# DIOT_signal_routing.net
KiCad netlist of a schematic drawn in Altium Designer
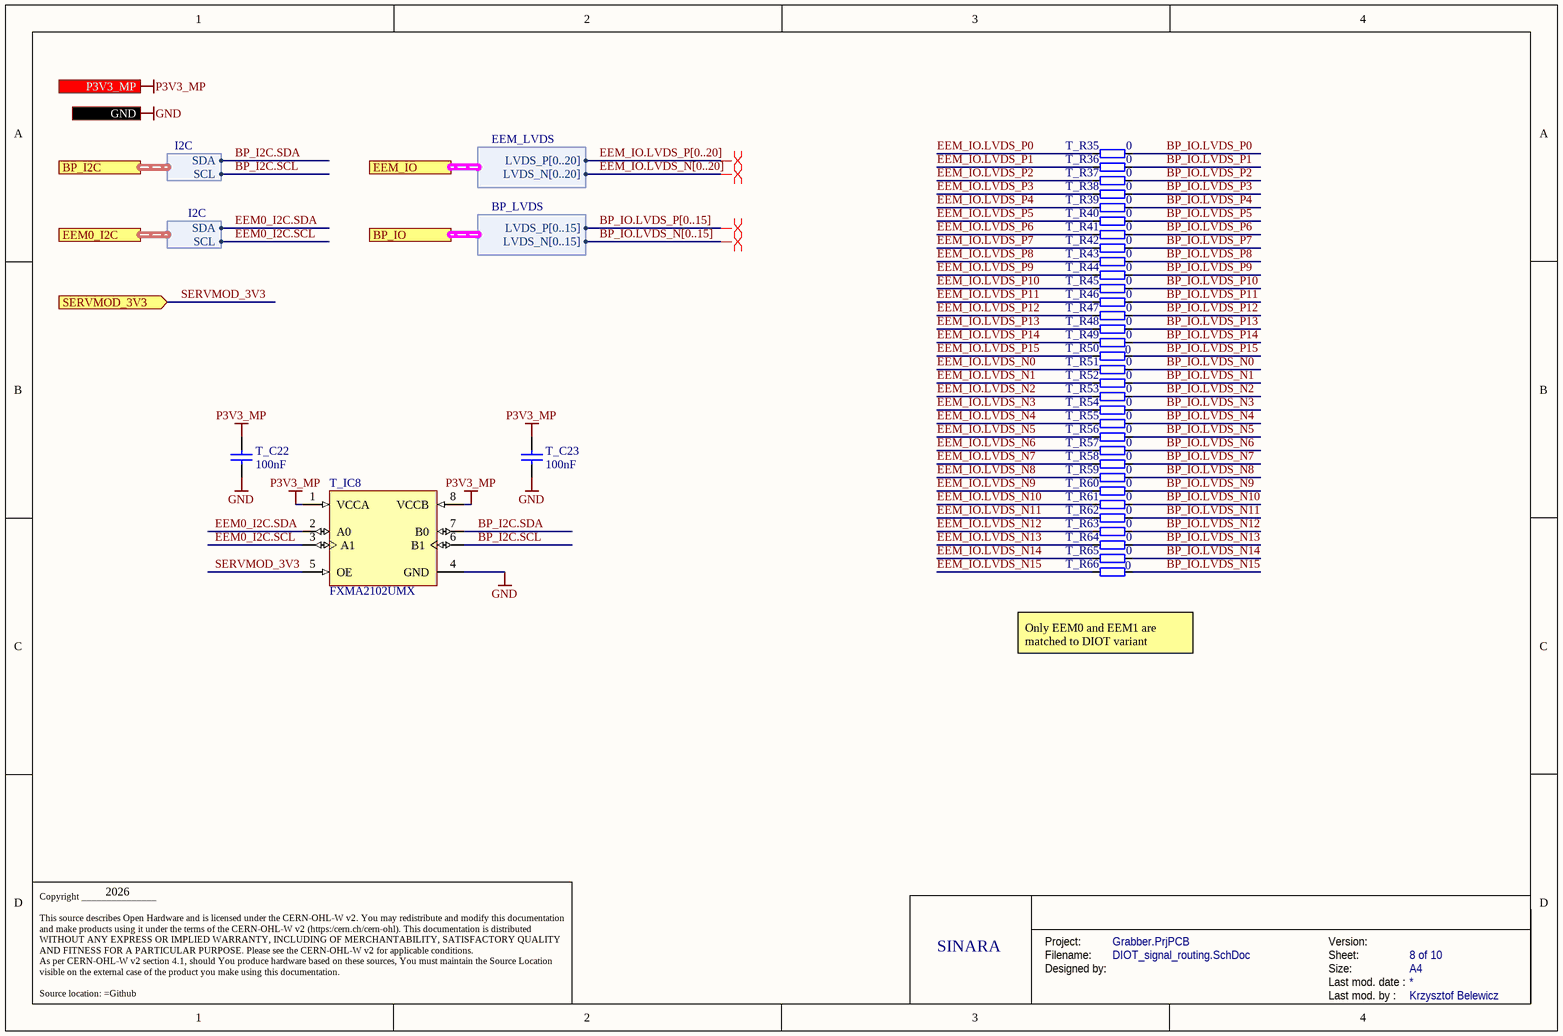
[diagram p0: DIOT_signal_routing.SchDoc]

(export (version "E")
  (design (tool "Eeschema 10.0.6"))
  (components
    (comp (ref "T_C22")
      (value "100nF")
      (footprint "CAPC1005X55N")
      (description "Non-polarised capacitor")
      (fields
        (field (name "PART NUMBER") "CC0402_100NF_50V_10%_X7R")
        (field (name "VOLTAGE") "50V")
        (field (name "AUTHOR") "CERN DEM MR")
      )
      (libsource (lib "Capacitors") (part "Capacitor - non polarized"))
    )
    (comp (ref "T_C23")
      (value "100nF")
      (footprint "CAPC1005X55N")
      (description "Non-polarised capacitor")
      (fields
        (field (name "PART NUMBER") "CC0402_100NF_50V_10%_X7R")
        (field (name "VOLTAGE") "50V")
        (field (name "AUTHOR") "CERN DEM MR")
      )
      (libsource (lib "Capacitors") (part "Capacitor - non polarized"))
    )
    (comp (ref "T_IC8")
      (value "FXMA2102UMX")
      (footprint "FXMA2102UMX")
      (description "Dual Supply 2-Bit Voltage Translator/Buffer/Repeater Isolator for I2C Applications")
      (fields (field (name "MANUFACTURER") "Onsemi"))
      (libsource (lib "TechnoSystem Workspace") (part "FXMA2102UMX"))
    )
    (comp (ref "T_R35")
      (value "0")
      (footprint "RESC1005X40N")
      (description "Resistor")
      (fields
        (field (name "PART NUMBER") "R0402_0R_JUMPER")
        (field (name "MANUFACTURER") "GENERIC")
        (field (name "AUTHOR") "CERN DEM JLC")
      )
      (libsource (lib "Resistors") (part "Resistor"))
    )
    (comp (ref "T_R36")
      (value "0")
      (footprint "RESC1005X40N")
      (description "Resistor")
      (fields
        (field (name "PART NUMBER") "R0402_0R_JUMPER")
        (field (name "MANUFACTURER") "GENERIC")
        (field (name "AUTHOR") "CERN DEM JLC")
      )
      (libsource (lib "Resistors") (part "Resistor"))
    )
    (comp (ref "T_R37")
      (value "0")
      (footprint "RESC1005X40N")
      (description "Resistor")
      (fields
        (field (name "PART NUMBER") "R0402_0R_JUMPER")
        (field (name "MANUFACTURER") "GENERIC")
        (field (name "AUTHOR") "CERN DEM JLC")
      )
      (libsource (lib "Resistors") (part "Resistor"))
    )
    (comp (ref "T_R38")
      (value "0")
      (footprint "RESC1005X40N")
      (description "Resistor")
      (fields
        (field (name "PART NUMBER") "R0402_0R_JUMPER")
        (field (name "MANUFACTURER") "GENERIC")
        (field (name "AUTHOR") "CERN DEM JLC")
      )
      (libsource (lib "Resistors") (part "Resistor"))
    )
    (comp (ref "T_R39")
      (value "0")
      (footprint "RESC1005X40N")
      (description "Resistor")
      (fields
        (field (name "PART NUMBER") "R0402_0R_JUMPER")
        (field (name "MANUFACTURER") "GENERIC")
        (field (name "AUTHOR") "CERN DEM JLC")
      )
      (libsource (lib "Resistors") (part "Resistor"))
    )
    (comp (ref "T_R40")
      (value "0")
      (footprint "RESC1005X40N")
      (description "Resistor")
      (fields
        (field (name "PART NUMBER") "R0402_0R_JUMPER")
        (field (name "MANUFACTURER") "GENERIC")
        (field (name "AUTHOR") "CERN DEM JLC")
      )
      (libsource (lib "Resistors") (part "Resistor"))
    )
    (comp (ref "T_R41")
      (value "0")
      (footprint "RESC1005X40N")
      (description "Resistor")
      (fields
        (field (name "PART NUMBER") "R0402_0R_JUMPER")
        (field (name "MANUFACTURER") "GENERIC")
        (field (name "AUTHOR") "CERN DEM JLC")
      )
      (libsource (lib "Resistors") (part "Resistor"))
    )
    (comp (ref "T_R42")
      (value "0")
      (footprint "RESC1005X40N")
      (description "Resistor")
      (fields
        (field (name "PART NUMBER") "R0402_0R_JUMPER")
        (field (name "MANUFACTURER") "GENERIC")
        (field (name "AUTHOR") "CERN DEM JLC")
      )
      (libsource (lib "Resistors") (part "Resistor"))
    )
    (comp (ref "T_R43")
      (value "0")
      (footprint "RESC1005X40N")
      (description "Resistor")
      (fields
        (field (name "PART NUMBER") "R0402_0R_JUMPER")
        (field (name "MANUFACTURER") "GENERIC")
        (field (name "AUTHOR") "CERN DEM JLC")
      )
      (libsource (lib "Resistors") (part "Resistor"))
    )
    (comp (ref "T_R44")
      (value "0")
      (footprint "RESC1005X40N")
      (description "Resistor")
      (fields
        (field (name "PART NUMBER") "R0402_0R_JUMPER")
        (field (name "MANUFACTURER") "GENERIC")
        (field (name "AUTHOR") "CERN DEM JLC")
      )
      (libsource (lib "Resistors") (part "Resistor"))
    )
    (comp (ref "T_R45")
      (value "0")
      (footprint "RESC1005X40N")
      (description "Resistor")
      (fields
        (field (name "PART NUMBER") "R0402_0R_JUMPER")
        (field (name "MANUFACTURER") "GENERIC")
        (field (name "AUTHOR") "CERN DEM JLC")
      )
      (libsource (lib "Resistors") (part "Resistor"))
    )
    (comp (ref "T_R46")
      (value "0")
      (footprint "RESC1005X40N")
      (description "Resistor")
      (fields
        (field (name "PART NUMBER") "R0402_0R_JUMPER")
        (field (name "MANUFACTURER") "GENERIC")
        (field (name "AUTHOR") "CERN DEM JLC")
      )
      (libsource (lib "Resistors") (part "Resistor"))
    )
    (comp (ref "T_R47")
      (value "0")
      (footprint "RESC1005X40N")
      (description "Resistor")
      (fields
        (field (name "PART NUMBER") "R0402_0R_JUMPER")
        (field (name "MANUFACTURER") "GENERIC")
        (field (name "AUTHOR") "CERN DEM JLC")
      )
      (libsource (lib "Resistors") (part "Resistor"))
    )
    (comp (ref "T_R48")
      (value "0")
      (footprint "RESC1005X40N")
      (description "Resistor")
      (fields
        (field (name "PART NUMBER") "R0402_0R_JUMPER")
        (field (name "MANUFACTURER") "GENERIC")
        (field (name "AUTHOR") "CERN DEM JLC")
      )
      (libsource (lib "Resistors") (part "Resistor"))
    )
    (comp (ref "T_R49")
      (value "0")
      (footprint "RESC1005X40N")
      (description "Resistor")
      (fields
        (field (name "PART NUMBER") "R0402_0R_JUMPER")
        (field (name "MANUFACTURER") "GENERIC")
        (field (name "AUTHOR") "CERN DEM JLC")
      )
      (libsource (lib "Resistors") (part "Resistor"))
    )
    (comp (ref "T_R50")
      (value "0")
      (footprint "RESC1005X40N")
      (description "Resistor")
      (fields
        (field (name "PART NUMBER") "R0402_0R_JUMPER")
        (field (name "MANUFACTURER") "GENERIC")
        (field (name "AUTHOR") "CERN DEM JLC")
      )
      (libsource (lib "Resistors") (part "Resistor"))
    )
    (comp (ref "T_R51")
      (value "0")
      (footprint "RESC1005X40N")
      (description "Resistor")
      (fields
        (field (name "PART NUMBER") "R0402_0R_JUMPER")
        (field (name "MANUFACTURER") "GENERIC")
        (field (name "AUTHOR") "CERN DEM JLC")
      )
      (libsource (lib "Resistors") (part "Resistor"))
    )
    (comp (ref "T_R52")
      (value "0")
      (footprint "RESC1005X40N")
      (description "Resistor")
      (fields
        (field (name "PART NUMBER") "R0402_0R_JUMPER")
        (field (name "MANUFACTURER") "GENERIC")
        (field (name "AUTHOR") "CERN DEM JLC")
      )
      (libsource (lib "Resistors") (part "Resistor"))
    )
    (comp (ref "T_R53")
      (value "0")
      (footprint "RESC1005X40N")
      (description "Resistor")
      (fields
        (field (name "PART NUMBER") "R0402_0R_JUMPER")
        (field (name "MANUFACTURER") "GENERIC")
        (field (name "AUTHOR") "CERN DEM JLC")
      )
      (libsource (lib "Resistors") (part "Resistor"))
    )
    (comp (ref "T_R54")
      (value "0")
      (footprint "RESC1005X40N")
      (description "Resistor")
      (fields
        (field (name "PART NUMBER") "R0402_0R_JUMPER")
        (field (name "MANUFACTURER") "GENERIC")
        (field (name "AUTHOR") "CERN DEM JLC")
      )
      (libsource (lib "Resistors") (part "Resistor"))
    )
    (comp (ref "T_R55")
      (value "0")
      (footprint "RESC1005X40N")
      (description "Resistor")
      (fields
        (field (name "PART NUMBER") "R0402_0R_JUMPER")
        (field (name "MANUFACTURER") "GENERIC")
        (field (name "AUTHOR") "CERN DEM JLC")
      )
      (libsource (lib "Resistors") (part "Resistor"))
    )
    (comp (ref "T_R56")
      (value "0")
      (footprint "RESC1005X40N")
      (description "Resistor")
      (fields
        (field (name "PART NUMBER") "R0402_0R_JUMPER")
        (field (name "MANUFACTURER") "GENERIC")
        (field (name "AUTHOR") "CERN DEM JLC")
      )
      (libsource (lib "Resistors") (part "Resistor"))
    )
    (comp (ref "T_R57")
      (value "0")
      (footprint "RESC1005X40N")
      (description "Resistor")
      (fields
        (field (name "PART NUMBER") "R0402_0R_JUMPER")
        (field (name "MANUFACTURER") "GENERIC")
        (field (name "AUTHOR") "CERN DEM JLC")
      )
      (libsource (lib "Resistors") (part "Resistor"))
    )
    (comp (ref "T_R58")
      (value "0")
      (footprint "RESC1005X40N")
      (description "Resistor")
      (fields
        (field (name "PART NUMBER") "R0402_0R_JUMPER")
        (field (name "MANUFACTURER") "GENERIC")
        (field (name "AUTHOR") "CERN DEM JLC")
      )
      (libsource (lib "Resistors") (part "Resistor"))
    )
    (comp (ref "T_R59")
      (value "0")
      (footprint "RESC1005X40N")
      (description "Resistor")
      (fields
        (field (name "PART NUMBER") "R0402_0R_JUMPER")
        (field (name "MANUFACTURER") "GENERIC")
        (field (name "AUTHOR") "CERN DEM JLC")
      )
      (libsource (lib "Resistors") (part "Resistor"))
    )
    (comp (ref "T_R60")
      (value "0")
      (footprint "RESC1005X40N")
      (description "Resistor")
      (fields
        (field (name "PART NUMBER") "R0402_0R_JUMPER")
        (field (name "MANUFACTURER") "GENERIC")
        (field (name "AUTHOR") "CERN DEM JLC")
      )
      (libsource (lib "Resistors") (part "Resistor"))
    )
    (comp (ref "T_R61")
      (value "0")
      (footprint "RESC1005X40N")
      (description "Resistor")
      (fields
        (field (name "PART NUMBER") "R0402_0R_JUMPER")
        (field (name "MANUFACTURER") "GENERIC")
        (field (name "AUTHOR") "CERN DEM JLC")
      )
      (libsource (lib "Resistors") (part "Resistor"))
    )
    (comp (ref "T_R62")
      (value "0")
      (footprint "RESC1005X40N")
      (description "Resistor")
      (fields
        (field (name "PART NUMBER") "R0402_0R_JUMPER")
        (field (name "MANUFACTURER") "GENERIC")
        (field (name "AUTHOR") "CERN DEM JLC")
      )
      (libsource (lib "Resistors") (part "Resistor"))
    )
    (comp (ref "T_R63")
      (value "0")
      (footprint "RESC1005X40N")
      (description "Resistor")
      (fields
        (field (name "PART NUMBER") "R0402_0R_JUMPER")
        (field (name "MANUFACTURER") "GENERIC")
        (field (name "AUTHOR") "CERN DEM JLC")
      )
      (libsource (lib "Resistors") (part "Resistor"))
    )
    (comp (ref "T_R64")
      (value "0")
      (footprint "RESC1005X40N")
      (description "Resistor")
      (fields
        (field (name "PART NUMBER") "R0402_0R_JUMPER")
        (field (name "MANUFACTURER") "GENERIC")
        (field (name "AUTHOR") "CERN DEM JLC")
      )
      (libsource (lib "Resistors") (part "Resistor"))
    )
    (comp (ref "T_R65")
      (value "0")
      (footprint "RESC1005X40N")
      (description "Resistor")
      (fields
        (field (name "PART NUMBER") "R0402_0R_JUMPER")
        (field (name "MANUFACTURER") "GENERIC")
        (field (name "AUTHOR") "CERN DEM JLC")
      )
      (libsource (lib "Resistors") (part "Resistor"))
    )
    (comp (ref "T_R66")
      (value "0")
      (footprint "RESC1005X40N")
      (description "Resistor")
      (fields
        (field (name "PART NUMBER") "R0402_0R_JUMPER")
        (field (name "MANUFACTURER") "GENERIC")
        (field (name "AUTHOR") "CERN DEM JLC")
      )
      (libsource (lib "Resistors") (part "Resistor"))
    )
  )
  (nets
    (net (code "14") (name "/BP_I2C.SCL") (class "Default")
      (node (ref "T_IC8") (pin "6") (pinfunction "B1_6") (pintype "bidirectional"))
    )
    (net (code "15") (name "/BP_I2C.SDA") (class "Default")
      (node (ref "T_IC8") (pin "7") (pinfunction "B0_7") (pintype "bidirectional"))
    )
    (net (code "16") (name "/BP_IO.LVDS_N0") (class "Default")
      (node (ref "T_R51") (pin "1") (pinfunction "1_1") (pintype "passive"))
    )
    (net (code "17") (name "/BP_IO.LVDS_N1") (class "Default")
      (node (ref "T_R52") (pin "1") (pinfunction "1_1") (pintype "passive"))
    )
    (net (code "18") (name "/BP_IO.LVDS_N2") (class "Default")
      (node (ref "T_R53") (pin "1") (pinfunction "1_1") (pintype "passive"))
    )
    (net (code "19") (name "/BP_IO.LVDS_N3") (class "Default")
      (node (ref "T_R54") (pin "1") (pinfunction "1_1") (pintype "passive"))
    )
    (net (code "20") (name "/BP_IO.LVDS_N4") (class "Default")
      (node (ref "T_R55") (pin "1") (pinfunction "1_1") (pintype "passive"))
    )
    (net (code "21") (name "/BP_IO.LVDS_N5") (class "Default")
      (node (ref "T_R56") (pin "1") (pinfunction "1_1") (pintype "passive"))
    )
    (net (code "22") (name "/BP_IO.LVDS_N6") (class "Default")
      (node (ref "T_R57") (pin "1") (pinfunction "1_1") (pintype "passive"))
    )
    (net (code "23") (name "/BP_IO.LVDS_N7") (class "Default")
      (node (ref "T_R58") (pin "1") (pinfunction "1_1") (pintype "passive"))
    )
    (net (code "24") (name "/BP_IO.LVDS_N8") (class "Default")
      (node (ref "T_R59") (pin "1") (pinfunction "1_1") (pintype "passive"))
    )
    (net (code "25") (name "/BP_IO.LVDS_N9") (class "Default")
      (node (ref "T_R60") (pin "1") (pinfunction "1_1") (pintype "passive"))
    )
    (net (code "26") (name "/BP_IO.LVDS_N10") (class "Default")
      (node (ref "T_R61") (pin "1") (pinfunction "1_1") (pintype "passive"))
    )
    (net (code "27") (name "/BP_IO.LVDS_N11") (class "Default")
      (node (ref "T_R62") (pin "1") (pinfunction "1_1") (pintype "passive"))
    )
    (net (code "28") (name "/BP_IO.LVDS_N12") (class "Default")
      (node (ref "T_R63") (pin "1") (pinfunction "1_1") (pintype "passive"))
    )
    (net (code "29") (name "/BP_IO.LVDS_N13") (class "Default")
      (node (ref "T_R64") (pin "1") (pinfunction "1_1") (pintype "passive"))
    )
    (net (code "30") (name "/BP_IO.LVDS_N14") (class "Default")
      (node (ref "T_R65") (pin "1") (pinfunction "1_1") (pintype "passive"))
    )
    (net (code "31") (name "/BP_IO.LVDS_N15") (class "Default")
      (node (ref "T_R66") (pin "2") (pinfunction "2_2") (pintype "passive"))
    )
    (net (code "32") (name "/BP_IO.LVDS_P0") (class "Default")
      (node (ref "T_R35") (pin "1") (pinfunction "1_1") (pintype "passive"))
    )
    (net (code "33") (name "/BP_IO.LVDS_P1") (class "Default")
      (node (ref "T_R36") (pin "1") (pinfunction "1_1") (pintype "passive"))
    )
    (net (code "34") (name "/BP_IO.LVDS_P2") (class "Default")
      (node (ref "T_R37") (pin "1") (pinfunction "1_1") (pintype "passive"))
    )
    (net (code "35") (name "/BP_IO.LVDS_P3") (class "Default")
      (node (ref "T_R38") (pin "1") (pinfunction "1_1") (pintype "passive"))
    )
    (net (code "36") (name "/BP_IO.LVDS_P4") (class "Default")
      (node (ref "T_R39") (pin "1") (pinfunction "1_1") (pintype "passive"))
    )
    (net (code "37") (name "/BP_IO.LVDS_P5") (class "Default")
      (node (ref "T_R40") (pin "1") (pinfunction "1_1") (pintype "passive"))
    )
    (net (code "38") (name "/BP_IO.LVDS_P6") (class "Default")
      (node (ref "T_R41") (pin "1") (pinfunction "1_1") (pintype "passive"))
    )
    (net (code "39") (name "/BP_IO.LVDS_P7") (class "Default")
      (node (ref "T_R42") (pin "1") (pinfunction "1_1") (pintype "passive"))
    )
    (net (code "40") (name "/BP_IO.LVDS_P8") (class "Default")
      (node (ref "T_R43") (pin "1") (pinfunction "1_1") (pintype "passive"))
    )
    (net (code "41") (name "/BP_IO.LVDS_P9") (class "Default")
      (node (ref "T_R44") (pin "1") (pinfunction "1_1") (pintype "passive"))
    )
    (net (code "42") (name "/BP_IO.LVDS_P10") (class "Default")
      (node (ref "T_R45") (pin "1") (pinfunction "1_1") (pintype "passive"))
    )
    (net (code "43") (name "/BP_IO.LVDS_P11") (class "Default")
      (node (ref "T_R46") (pin "1") (pinfunction "1_1") (pintype "passive"))
    )
    (net (code "44") (name "/BP_IO.LVDS_P12") (class "Default")
      (node (ref "T_R47") (pin "1") (pinfunction "1_1") (pintype "passive"))
    )
    (net (code "45") (name "/BP_IO.LVDS_P13") (class "Default")
      (node (ref "T_R48") (pin "1") (pinfunction "1_1") (pintype "passive"))
    )
    (net (code "46") (name "/BP_IO.LVDS_P14") (class "Default")
      (node (ref "T_R49") (pin "1") (pinfunction "1_1") (pintype "passive"))
    )
    (net (code "47") (name "/BP_IO.LVDS_P15") (class "Default")
      (node (ref "T_R50") (pin "2") (pinfunction "2_2") (pintype "passive"))
    )
    (net (code "50") (name "/EEM0_I2C.SCL") (class "Default")
      (node (ref "T_IC8") (pin "3") (pinfunction "A1_3") (pintype "bidirectional"))
    )
    (net (code "51") (name "/EEM0_I2C.SDA") (class "Default")
      (node (ref "T_IC8") (pin "2") (pinfunction "A0_2") (pintype "bidirectional"))
    )
    (net (code "52") (name "/EEM_IO.LVDS_N0") (class "Default")
      (node (ref "T_R51") (pin "2") (pinfunction "2_2") (pintype "passive"))
    )
    (net (code "53") (name "/EEM_IO.LVDS_N1") (class "Default")
      (node (ref "T_R52") (pin "2") (pinfunction "2_2") (pintype "passive"))
    )
    (net (code "54") (name "/EEM_IO.LVDS_N2") (class "Default")
      (node (ref "T_R53") (pin "2") (pinfunction "2_2") (pintype "passive"))
    )
    (net (code "55") (name "/EEM_IO.LVDS_N3") (class "Default")
      (node (ref "T_R54") (pin "2") (pinfunction "2_2") (pintype "passive"))
    )
    (net (code "56") (name "/EEM_IO.LVDS_N4") (class "Default")
      (node (ref "T_R55") (pin "2") (pinfunction "2_2") (pintype "passive"))
    )
    (net (code "57") (name "/EEM_IO.LVDS_N5") (class "Default")
      (node (ref "T_R56") (pin "2") (pinfunction "2_2") (pintype "passive"))
    )
    (net (code "58") (name "/EEM_IO.LVDS_N6") (class "Default")
      (node (ref "T_R57") (pin "2") (pinfunction "2_2") (pintype "passive"))
    )
    (net (code "59") (name "/EEM_IO.LVDS_N7") (class "Default")
      (node (ref "T_R58") (pin "2") (pinfunction "2_2") (pintype "passive"))
    )
    (net (code "60") (name "/EEM_IO.LVDS_N8") (class "Default")
      (node (ref "T_R59") (pin "2") (pinfunction "2_2") (pintype "passive"))
    )
    (net (code "61") (name "/EEM_IO.LVDS_N9") (class "Default")
      (node (ref "T_R60") (pin "2") (pinfunction "2_2") (pintype "passive"))
    )
    (net (code "62") (name "/EEM_IO.LVDS_N10") (class "Default")
      (node (ref "T_R61") (pin "2") (pinfunction "2_2") (pintype "passive"))
    )
    (net (code "63") (name "/EEM_IO.LVDS_N11") (class "Default")
      (node (ref "T_R62") (pin "2") (pinfunction "2_2") (pintype "passive"))
    )
    (net (code "64") (name "/EEM_IO.LVDS_N12") (class "Default")
      (node (ref "T_R63") (pin "2") (pinfunction "2_2") (pintype "passive"))
    )
    (net (code "65") (name "/EEM_IO.LVDS_N13") (class "Default")
      (node (ref "T_R64") (pin "2") (pinfunction "2_2") (pintype "passive"))
    )
    (net (code "66") (name "/EEM_IO.LVDS_N14") (class "Default")
      (node (ref "T_R65") (pin "2") (pinfunction "2_2") (pintype "passive"))
    )
    (net (code "67") (name "/EEM_IO.LVDS_N15") (class "Default")
      (node (ref "T_R66") (pin "1") (pinfunction "1_1") (pintype "passive"))
    )
    (net (code "69") (name "/EEM_IO.LVDS_P0") (class "Default")
      (node (ref "T_R35") (pin "2") (pinfunction "2_2") (pintype "passive"))
    )
    (net (code "70") (name "/EEM_IO.LVDS_P1") (class "Default")
      (node (ref "T_R36") (pin "2") (pinfunction "2_2") (pintype "passive"))
    )
    (net (code "71") (name "/EEM_IO.LVDS_P2") (class "Default")
      (node (ref "T_R37") (pin "2") (pinfunction "2_2") (pintype "passive"))
    )
    (net (code "72") (name "/EEM_IO.LVDS_P3") (class "Default")
      (node (ref "T_R38") (pin "2") (pinfunction "2_2") (pintype "passive"))
    )
    (net (code "73") (name "/EEM_IO.LVDS_P4") (class "Default")
      (node (ref "T_R39") (pin "2") (pinfunction "2_2") (pintype "passive"))
    )
    (net (code "74") (name "/EEM_IO.LVDS_P5") (class "Default")
      (node (ref "T_R40") (pin "2") (pinfunction "2_2") (pintype "passive"))
    )
    (net (code "75") (name "/EEM_IO.LVDS_P6") (class "Default")
      (node (ref "T_R41") (pin "2") (pinfunction "2_2") (pintype "passive"))
    )
    (net (code "76") (name "/EEM_IO.LVDS_P7") (class "Default")
      (node (ref "T_R42") (pin "2") (pinfunction "2_2") (pintype "passive"))
    )
    (net (code "77") (name "/EEM_IO.LVDS_P8") (class "Default")
      (node (ref "T_R43") (pin "2") (pinfunction "2_2") (pintype "passive"))
    )
    (net (code "78") (name "/EEM_IO.LVDS_P9") (class "Default")
      (node (ref "T_R44") (pin "2") (pinfunction "2_2") (pintype "passive"))
    )
    (net (code "79") (name "/EEM_IO.LVDS_P10") (class "Default")
      (node (ref "T_R45") (pin "2") (pinfunction "2_2") (pintype "passive"))
    )
    (net (code "80") (name "/EEM_IO.LVDS_P11") (class "Default")
      (node (ref "T_R46") (pin "2") (pinfunction "2_2") (pintype "passive"))
    )
    (net (code "81") (name "/EEM_IO.LVDS_P12") (class "Default")
      (node (ref "T_R47") (pin "2") (pinfunction "2_2") (pintype "passive"))
    )
    (net (code "82") (name "/EEM_IO.LVDS_P13") (class "Default")
      (node (ref "T_R48") (pin "2") (pinfunction "2_2") (pintype "passive"))
    )
    (net (code "83") (name "/EEM_IO.LVDS_P14") (class "Default")
      (node (ref "T_R49") (pin "2") (pinfunction "2_2") (pintype "passive"))
    )
    (net (code "84") (name "/EEM_IO.LVDS_P15") (class "Default")
      (node (ref "T_R50") (pin "1") (pinfunction "1_1") (pintype "passive"))
    )
    (net (code "86") (name "/SERVMOD_3V3") (class "Default")
      (node (ref "T_IC8") (pin "5") (pinfunction "OE_5") (pintype "input"))
    )
    (net (code "89") (name "GND") (class "Default")
      (node (ref "T_C22") (pin "1") (pinfunction "1_1") (pintype "passive"))
      (node (ref "T_C23") (pin "1") (pinfunction "1_1") (pintype "passive"))
      (node (ref "T_IC8") (pin "4") (pinfunction "GND_4") (pintype "power_in"))
    )
    (net (code "90") (name "P3V3_MP") (class "Default")
      (node (ref "T_C22") (pin "2") (pinfunction "2_2") (pintype "passive"))
      (node (ref "T_C23") (pin "2") (pinfunction "2_2") (pintype "passive"))
      (node (ref "T_IC8") (pin "1") (pinfunction "VCCA_1") (pintype "input"))
      (node (ref "T_IC8") (pin "8") (pinfunction "VCCB_8") (pintype "input"))
    )
  )
)
